# untitled.net
KiCad netlist of a schematic drawn in EAGLE
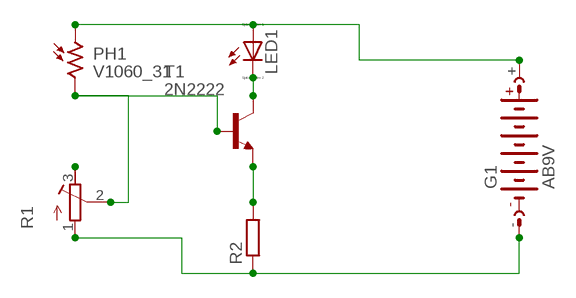
[diagram p0: schematic, sheet 1]

(export (version "E")
  (design (tool "Eeschema 10.0.6"))
  (components
    (comp (ref "G1")
      (value "AB9V")
      (footprint "eagle-import:AB9V")
      (libsource (lib "eagle-import") (part "AB9V"))
    )
    (comp (ref "LED1")
      (value "LED_ELD260")
      (footprint "eagle-import:LED_LD260")
      (libsource (lib "eagle-import") (part "LED_ELD260"))
    )
    (comp (ref "PH1")
      (value "V1060_31")
      (footprint "eagle-import:TO-5_V10")
      (libsource (lib "eagle-import") (part "?1060V_31"))
    )
    (comp (ref "R1")
      (value "R-TRIMM4G/J")
      (footprint "eagle-import:RTRIM4G_J")
      (libsource (lib "eagle-import") (part "R-TRIMM4G/J"))
    )
    (comp (ref "R2")
      (value "R-EU_0204/2V")
      (footprint "eagle-import:0204V")
      (libsource (lib "eagle-import") (part "R-EU_0204/2V"))
    )
    (comp (ref "T1")
      (value "2N2222")
      (footprint "eagle-import:TO18")
      (libsource (lib "eagle-import") (part "2N2222"))
    )
  )
  (nets
    (net (code "1") (name "Net-(G1-Pad+)") (class "Default")
      (node (ref "G1") (pin "+") (pinfunction "+_+") (pintype "passive"))
      (node (ref "LED1") (pin "A") (pinfunction "A_A") (pintype "passive"))
      (node (ref "PH1") (pin "1") (pinfunction "1_1") (pintype "passive"))
    )
    (net (code "2") (name "Net-(LED1-C)") (class "Default")
      (node (ref "LED1") (pin "K") (pinfunction "C_K") (pintype "passive"))
      (node (ref "T1") (pin "3") (pinfunction "C_3") (pintype "passive"))
    )
    (net (code "3") (name "Net-(R1-A)") (class "Default")
      (node (ref "G1") (pin "-") (pinfunction "-_-") (pintype "passive"))
      (node (ref "R1") (pin "1") (pinfunction "A_1") (pintype "passive"))
      (node (ref "R2") (pin "1") (pinfunction "1_1") (pintype "passive"))
    )
    (net (code "4") (name "Net-(R1-S)") (class "Default")
      (node (ref "PH1") (pin "2") (pinfunction "2_2") (pintype "passive"))
      (node (ref "R1") (pin "2") (pinfunction "S_2") (pintype "passive"))
      (node (ref "T1") (pin "2") (pinfunction "B_2") (pintype "passive"))
    )
    (net (code "5") (name "Net-(T1-E)") (class "Default")
      (node (ref "R2") (pin "2") (pinfunction "2_2") (pintype "passive"))
      (node (ref "T1") (pin "1") (pinfunction "E_1") (pintype "passive"))
    )
    (net (code "6") (name "unconnected-(R1-E-Pad3)") (class "Default")
      (node (ref "R1") (pin "3") (pinfunction "E_3") (pintype "passive"))
    )
  )
)
